# USB2_0HUB.net
KiCad netlist of a schematic drawn in Altium Designer
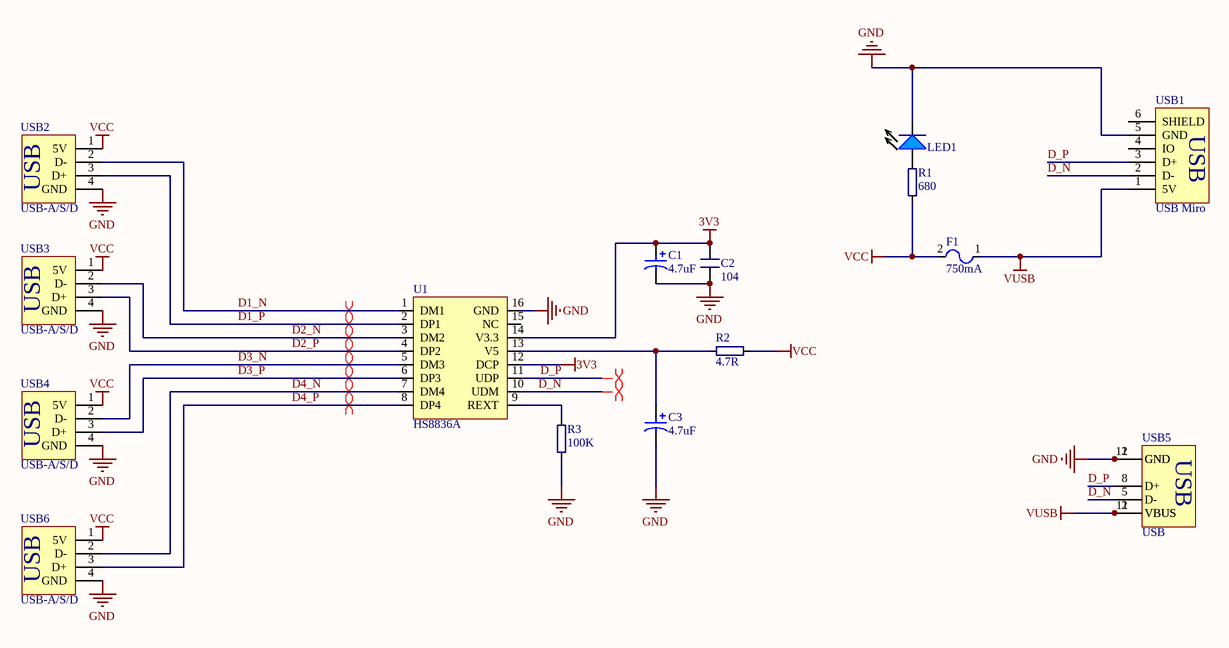
[diagram p0: USB2.0HUB.SchDoc]

(export (version "E")
  (design (tool "Eeschema 10.0.6"))
  (components
    (comp (ref "C1")
      (value "4.7uF")
      (footprint "SMD-C-AL-4*5.4")
      (libsource (lib "arduino") (part "SMD-C-AL-4*5.4"))
    )
    (comp (ref "C2")
      (value "104")
      (footprint "SMD-C-0805")
      (description "贴片瓷片电容")
      (libsource (lib "arduino") (part "SMD-C-0805"))
    )
    (comp (ref "C3")
      (value "4.7uF")
      (footprint "SMD-C-AL-4*5.4")
      (libsource (lib "arduino") (part "SMD-C-AL-4*5.4"))
    )
    (comp (ref "F1")
      (value "750mA")
      (footprint "SMD-F-0805")
      (description "保险丝贴片自恢复")
      (libsource (lib "arduino") (part "SMD-F-0805"))
    )
    (comp (ref "LED1")
      (value "SMD-LED_Blue")
      (footprint "SMD-LED-0805B")
      (libsource (lib "arduino") (part "SMD-LED_Blue"))
    )
    (comp (ref "R1") (value "680") (footprint "SMD-R-0805") (libsource (lib "arduino") (part "SMD-R-0805")))
    (comp (ref "R2") (value "4.7R") (footprint "SMD-R-0805") (libsource (lib "arduino") (part "SMD-R-0805")))
    (comp (ref "R3") (value "100K") (footprint "SMD-R-0805") (libsource (lib "arduino") (part "SMD-R-0805")))
    (comp (ref "U1")
      (value "HS8836A")
      (footprint "SMD-U-SOP-16")
      (libsource (lib "arduino") (part "SMD-IC-HS8836A"))
    )
    (comp (ref "USB1")
      (value "USB Miro")
      (footprint "USB MICRO")
      (description "USB")
      (libsource (lib "arduino") (part "USB MICRO"))
    )
    (comp (ref "USB2")
      (value "USB-A/S/D")
      (footprint "DIP-USB-A/S_D")
      (libsource (lib "arduino") (part "DIP-USB-A/S_D"))
    )
    (comp (ref "USB3")
      (value "USB-A/S/D")
      (footprint "DIP-USB-A/S_D")
      (libsource (lib "arduino") (part "DIP-USB-A/S_D"))
    )
    (comp (ref "USB4")
      (value "USB-A/S/D")
      (footprint "DIP-USB-A/S_D")
      (libsource (lib "arduino") (part "DIP-USB-A/S_D"))
    )
    (comp (ref "USB5")
      (value "USB")
      (footprint "SMD-USB-typeC-12")
      (libsource (lib "arduino") (part "SMD-TYPEC-12"))
    )
    (comp (ref "USB6")
      (value "USB-A/S/D")
      (footprint "DIP-USB-A/S_D")
      (libsource (lib "arduino") (part "DIP-USB-A/S_D"))
    )
  )
  (nets
    (net (code "1") (name "/D1_N") (class "Default")
      (node (ref "U1") (pin "1") (pinfunction "DM1_1") (pintype "passive"))
      (node (ref "USB2") (pin "2") (pinfunction "D-_2") (pintype "passive"))
    )
    (net (code "2") (name "/D1_P") (class "Default")
      (node (ref "U1") (pin "2") (pinfunction "DP1_2") (pintype "passive"))
      (node (ref "USB2") (pin "3") (pinfunction "D+_3") (pintype "passive"))
    )
    (net (code "3") (name "/D2_N") (class "Default")
      (node (ref "U1") (pin "3") (pinfunction "DM2_3") (pintype "passive"))
      (node (ref "USB3") (pin "2") (pinfunction "D-_2") (pintype "passive"))
    )
    (net (code "4") (name "/D2_P") (class "Default")
      (node (ref "U1") (pin "4") (pinfunction "DP2_4") (pintype "passive"))
      (node (ref "USB3") (pin "3") (pinfunction "D+_3") (pintype "passive"))
    )
    (net (code "5") (name "/D3_N") (class "Default")
      (node (ref "U1") (pin "5") (pinfunction "DM3_5") (pintype "passive"))
      (node (ref "USB4") (pin "2") (pinfunction "D-_2") (pintype "passive"))
    )
    (net (code "6") (name "/D3_P") (class "Default")
      (node (ref "U1") (pin "6") (pinfunction "DP3_6") (pintype "passive"))
      (node (ref "USB4") (pin "3") (pinfunction "D+_3") (pintype "passive"))
    )
    (net (code "7") (name "/D4_N") (class "Default")
      (node (ref "U1") (pin "7") (pinfunction "DM4_7") (pintype "passive"))
      (node (ref "USB6") (pin "2") (pinfunction "D-_2") (pintype "passive"))
    )
    (net (code "8") (name "/D4_P") (class "Default")
      (node (ref "U1") (pin "8") (pinfunction "DP4_8") (pintype "passive"))
      (node (ref "USB6") (pin "3") (pinfunction "D+_3") (pintype "passive"))
    )
    (net (code "9") (name "/D_N") (class "Default")
      (node (ref "U1") (pin "10") (pinfunction "UDM_10") (pintype "passive"))
      (node (ref "USB1") (pin "2") (pinfunction "D-_2") (pintype "passive"))
      (node (ref "USB5") (pin "5") (pinfunction "D-_5") (pintype "passive"))
    )
    (net (code "10") (name "/D_P") (class "Default")
      (node (ref "U1") (pin "11") (pinfunction "UDP_11") (pintype "passive"))
      (node (ref "USB1") (pin "3") (pinfunction "D+_3") (pintype "passive"))
      (node (ref "USB5") (pin "8") (pinfunction "D+_8") (pintype "passive"))
    )
    (net (code "11") (name "3V3") (class "Default")
      (node (ref "C1") (pin "1") (pinfunction "1_1") (pintype "passive"))
      (node (ref "C2") (pin "2") (pintype "passive"))
      (node (ref "U1") (pin "12") (pinfunction "DCP_12") (pintype "passive"))
      (node (ref "U1") (pin "14") (pinfunction "V3.3_14") (pintype "passive"))
    )
    (net (code "12") (name "GND") (class "Default")
      (node (ref "C1") (pin "2") (pinfunction "2_2") (pintype "passive"))
      (node (ref "C2") (pin "1") (pintype "passive"))
      (node (ref "C3") (pin "2") (pinfunction "2_2") (pintype "passive"))
      (node (ref "LED1") (pin "2") (pinfunction "2_2") (pintype "passive"))
      (node (ref "R3") (pin "1") (pintype "passive"))
      (node (ref "U1") (pin "16") (pinfunction "GND_16") (pintype "passive"))
      (node (ref "USB1") (pin "5") (pinfunction "GND_5") (pintype "passive"))
      (node (ref "USB2") (pin "4") (pinfunction "GND_4") (pintype "passive"))
      (node (ref "USB3") (pin "4") (pinfunction "GND_4") (pintype "passive"))
      (node (ref "USB4") (pin "4") (pinfunction "GND_4") (pintype "passive"))
      (node (ref "USB5") (pin "1") (pinfunction "GND_1") (pintype "passive"))
      (node (ref "USB5") (pin "12") (pinfunction "GND_12") (pintype "passive"))
      (node (ref "USB6") (pin "4") (pinfunction "GND_4") (pintype "passive"))
    )
    (net (code "13") (name "Net-(LED1-Pad1)") (class "Default")
      (node (ref "LED1") (pin "1") (pinfunction "1_1") (pintype "passive"))
      (node (ref "R1") (pin "1") (pintype "passive"))
    )
    (net (code "14") (name "Net-(U1-REXT)") (class "Default")
      (node (ref "R3") (pin "2") (pintype "passive"))
      (node (ref "U1") (pin "9") (pinfunction "REXT_9") (pintype "passive"))
    )
    (net (code "15") (name "Net-(U1-V5)") (class "Default")
      (node (ref "C3") (pin "1") (pinfunction "1_1") (pintype "passive"))
      (node (ref "R2") (pin "2") (pintype "passive"))
      (node (ref "U1") (pin "13") (pinfunction "V5_13") (pintype "passive"))
    )
    (net (code "16") (name "VCC") (class "Default")
      (node (ref "F1") (pin "2") (pinfunction "2_2") (pintype "passive"))
      (node (ref "R1") (pin "2") (pintype "passive"))
      (node (ref "R2") (pin "1") (pintype "passive"))
      (node (ref "USB2") (pin "1") (pinfunction "5V_1") (pintype "passive"))
      (node (ref "USB3") (pin "1") (pinfunction "5V_1") (pintype "passive"))
      (node (ref "USB4") (pin "1") (pinfunction "5V_1") (pintype "passive"))
      (node (ref "USB6") (pin "1") (pinfunction "5V_1") (pintype "passive"))
    )
    (net (code "17") (name "VUSB") (class "Default")
      (node (ref "F1") (pin "1") (pinfunction "1_1") (pintype "passive"))
      (node (ref "USB1") (pin "1") (pinfunction "5V_1") (pintype "passive"))
      (node (ref "USB5") (pin "11") (pinfunction "VBUS_11") (pintype "passive"))
      (node (ref "USB5") (pin "2") (pinfunction "VBUS_2") (pintype "passive"))
    )
    (net (code "18") (name "unconnected-(U1-NC-Pad15)") (class "Default")
      (node (ref "U1") (pin "15") (pinfunction "NC_15") (pintype "passive"))
    )
    (net (code "19") (name "unconnected-(USB1-IO-Pad4)") (class "Default")
      (node (ref "USB1") (pin "4") (pinfunction "IO_4") (pintype "passive"))
    )
    (net (code "20") (name "unconnected-(USB1-SHIELD-Pad6)") (class "Default")
      (node (ref "USB1") (pin "6") (pinfunction "SHIELD_6") (pintype "passive"))
    )
  )
)
